# Servos_controller.net
KiCad netlist of a schematic drawn in Altium Designer
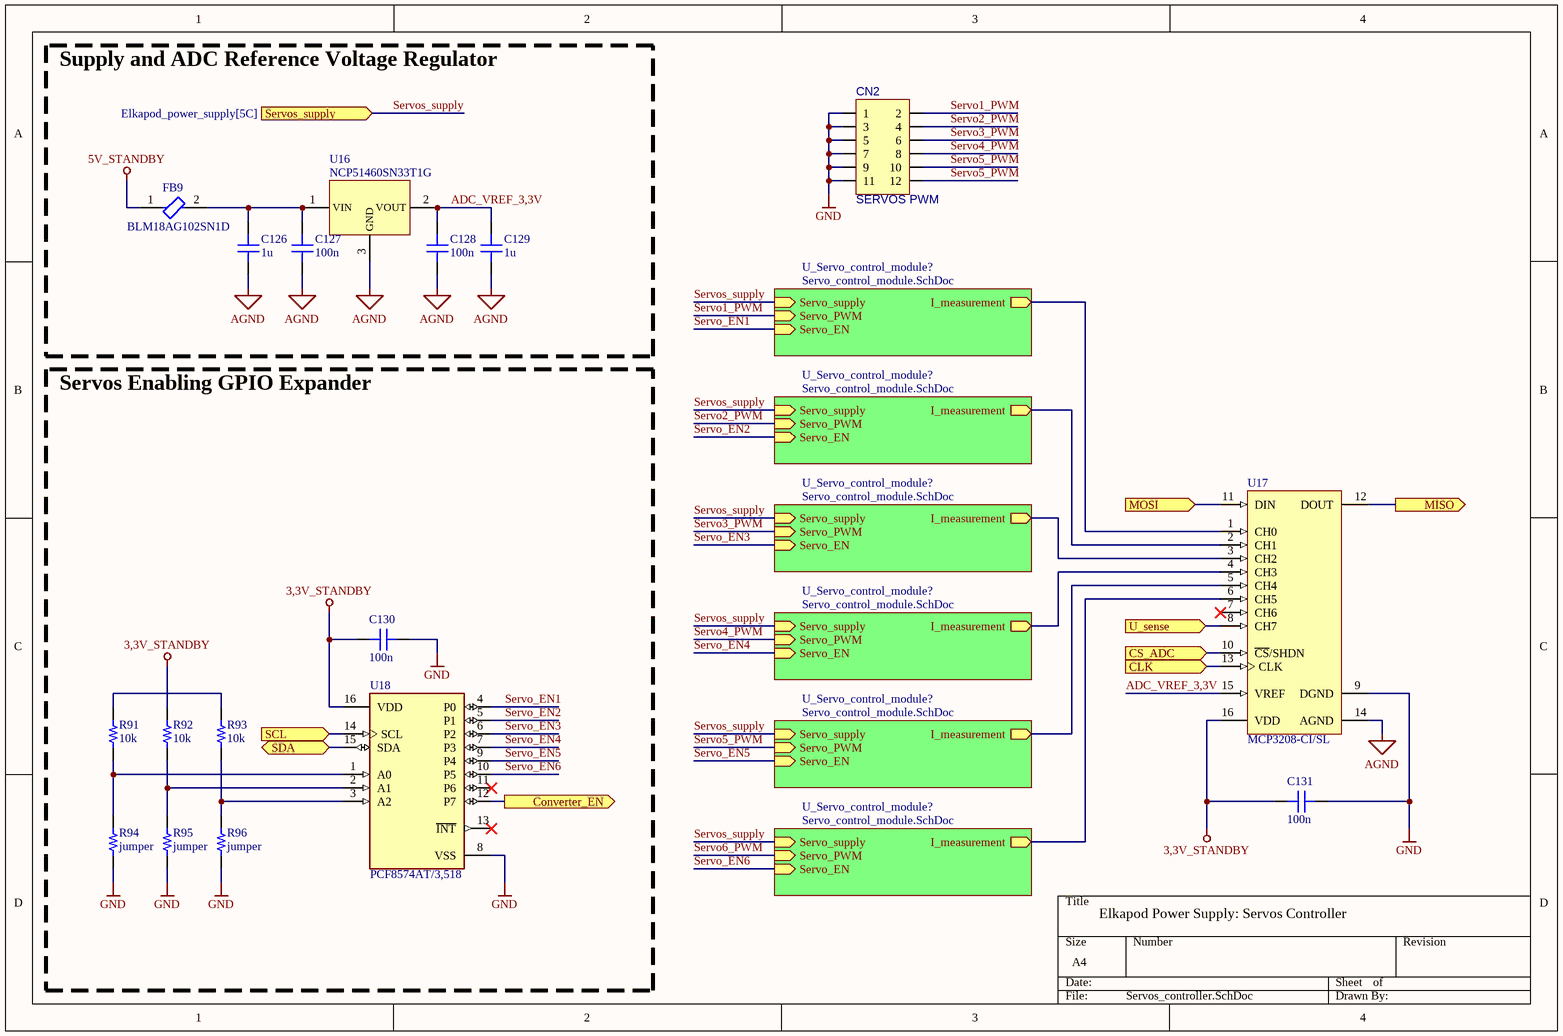
[diagram p0: Servos_controller.SchDoc]

(export (version "E")
  (design (tool "Eeschema 10.0.6"))
  (components
    (comp (ref "C126")
      (value "1u")
      (footprint "CAP 0603_1608")
      (description "CAP CER 1uF 16V X5R 0603")
      (fields (field (name "PART NUMBER") "C0603C272F3GAC7867") (field (name "MANUFACTURER") "KEMET"))
      (libsource (lib "Celestial Altium Library - altium_library") (part "Capacitor"))
    )
    (comp (ref "C127")
      (value "100n")
      (footprint "CAP 0603_1608")
      (description "CAP CER 100nF 25V X5R 0603")
      (fields (field (name "PART NUMBER") "C0603C272F3GAC7867") (field (name "MANUFACTURER") "KEMET"))
      (libsource (lib "Celestial Altium Library - altium_library") (part "Capacitor"))
    )
    (comp (ref "C128")
      (value "100n")
      (footprint "CAP 0603_1608")
      (description "CAP CER 100nF 25V X5R 0603")
      (fields (field (name "PART NUMBER") "C0603C272F3GAC7867") (field (name "MANUFACTURER") "KEMET"))
      (libsource (lib "Celestial Altium Library - altium_library") (part "Capacitor"))
    )
    (comp (ref "C129")
      (value "1u")
      (footprint "CAP 0603_1608")
      (description "CAP CER 1uF 16V X5R 0603")
      (fields (field (name "PART NUMBER") "C0603C272F3GAC7867") (field (name "MANUFACTURER") "KEMET"))
      (libsource (lib "Celestial Altium Library - altium_library") (part "Capacitor"))
    )
    (comp (ref "C130")
      (value "100n")
      (footprint "CAP 0603_1608")
      (description "CAP CER 100nF 25V X5R 0603")
      (fields (field (name "PART NUMBER") "C0603C272F3GAC7867") (field (name "MANUFACTURER") "KEMET"))
      (libsource (lib "Celestial Altium Library - altium_library") (part "Capacitor"))
    )
    (comp (ref "C131")
      (value "100n")
      (footprint "CAP 0603_1608")
      (description "CAP CER 100nF 25V X5R 0603")
      (fields (field (name "PART NUMBER") "C0603C272F3GAC7867") (field (name "MANUFACTURER") "KEMET"))
      (libsource (lib "Celestial Altium Library - altium_library") (part "Capacitor"))
    )
    (comp (ref "CN2") (value "SERVOS PWM") (footprint "IDC12") (libsource (lib "idc") (part "CN_6x2")))
    (comp (ref "FB9")
      (value "BLM18AG102SN1D")
      (footprint "FP-BLM18-0_15-t0_8-MFG")
      (description "Chip Ferrite Bead, 0603, 1000Ω @ 100MHz, 0.5Ω, 25%, 450mA")
      (fields (field (name "TOLERANCE") "25%"))
      (libsource (lib "Altium Content Vault") (part "5f30dd21d616792df468990f7003faa"))
    )
    (comp (ref "R91")
      (value "10k")
      (footprint "RES 0603_1608")
      (description "RES 10K OHM 1% 0,1W 0603")
      (fields
        (field (name "PART NUMBER") "RNCS0603BKE10K0")
        (field (name "MANUFACTURER") "Stackpole Electronics Inc")
      )
      (libsource (lib "Celestial Altium Library - altium_library") (part "Resistor"))
    )
    (comp (ref "R92")
      (value "10k")
      (footprint "RES 0603_1608")
      (description "RES 10K OHM 1% 0,1W 0603")
      (fields
        (field (name "PART NUMBER") "RNCS0603BKE10K0")
        (field (name "MANUFACTURER") "Stackpole Electronics Inc")
      )
      (libsource (lib "Celestial Altium Library - altium_library") (part "Resistor"))
    )
    (comp (ref "R93")
      (value "10k")
      (footprint "RES 0603_1608")
      (description "RES 10K OHM 1% 0,1W 0603")
      (fields
        (field (name "PART NUMBER") "RNCS0603BKE10K0")
        (field (name "MANUFACTURER") "Stackpole Electronics Inc")
      )
      (libsource (lib "Celestial Altium Library - altium_library") (part "Resistor"))
    )
    (comp (ref "R94")
      (value "jumper")
      (footprint "RES 0603_1608")
      (description "RES 0 OHM 1% 0,1W 0603")
      (fields
        (field (name "PART NUMBER") "RNCS0603BKE10K0")
        (field (name "MANUFACTURER") "Stackpole Electronics Inc")
      )
      (libsource (lib "Celestial Altium Library - altium_library") (part "Resistor"))
    )
    (comp (ref "R95")
      (value "jumper")
      (footprint "RES 0603_1608")
      (description "RES 0 OHM 1% 0,1W 0603")
      (fields
        (field (name "PART NUMBER") "RNCS0603BKE10K0")
        (field (name "MANUFACTURER") "Stackpole Electronics Inc")
      )
      (libsource (lib "Celestial Altium Library - altium_library") (part "Resistor"))
    )
    (comp (ref "R96")
      (value "jumper")
      (footprint "RES 0603_1608")
      (description "RES 0 OHM 1% 0,1W 0603")
      (fields
        (field (name "PART NUMBER") "RNCS0603BKE10K0")
        (field (name "MANUFACTURER") "Stackpole Electronics Inc")
      )
      (libsource (lib "Celestial Altium Library - altium_library") (part "Resistor"))
    )
    (comp (ref "U16")
      (value "NCP51460SN33T1G")
      (footprint "SOT23-3")
      (description "Low power precision voltage reference; Iout = 20mA")
      (libsource (lib "My_voltage_regulators") (part "NCP51460SN33T1G"))
    )
    (comp (ref "U17")
      (value "MCP3208-CI/SL")
      (footprint "SOIC-SL16_M")
      (libsource (lib "Altium Content Vault") (part "CON-ADC-MCP3008-16"))
    )
    (comp (ref "U18")
      (value "PCF8574AT/3,518")
      (footprint "FP-SOT162-1-MFG")
      (description "IC I/O EXPANDER I2C 8B 16SOIC")
      (fields
        (field (name "MANUFACTURER") "NXP Semiconductors")
        (field (name "OCTOPART") "https://octopart.com/pcf8574at%2F3%2C518-nxp+semiconductors-11541925")
      )
      (libsource (lib "Altium Content Vault") (part "f7fde53ce59de981fb0b266a4e103eb"))
    )
  )
  (nets
    (net (code "1") (name "/ADC_VREF_3,3V") (class "Default")
      (node (ref "C128") (pin "2") (pinfunction "2_2") (pintype "passive"))
      (node (ref "C129") (pin "2") (pinfunction "2_2") (pintype "passive"))
      (node (ref "U16") (pin "2") (pinfunction "VOUT_2") (pintype "passive"))
      (node (ref "U17") (pin "15") (pinfunction "VREF_15") (pintype "input"))
    )
    (net (code "2") (name "/CLK") (class "Default")
      (node (ref "U17") (pin "13") (pinfunction "CLK_13") (pintype "input"))
    )
    (net (code "3") (name "/CS_ADC") (class "Default")
      (node (ref "U17") (pin "10") (pinfunction "~{CS}/SHDN_10") (pintype "input"))
    )
    (net (code "4") (name "/Converter_EN") (class "Default")
      (node (ref "U18") (pin "12") (pinfunction "P7_12") (pintype "bidirectional"))
    )
    (net (code "5") (name "/I_measurement") (class "Default")
      (node (ref "U17") (pin "3") (pinfunction "CH2_3") (pintype "input"))
    )
    (net (code "6") (name "/I_measurement_1") (class "Default")
      (node (ref "U17") (pin "4") (pinfunction "CH3_4") (pintype "input"))
    )
    (net (code "7") (name "/I_measurement_2") (class "Default")
      (node (ref "U17") (pin "5") (pinfunction "CH4_5") (pintype "input"))
    )
    (net (code "8") (name "/I_measurement_3") (class "Default")
      (node (ref "U17") (pin "6") (pinfunction "CH5_6") (pintype "input"))
    )
    (net (code "9") (name "/I_measurement_4") (class "Default")
      (node (ref "U17") (pin "1") (pinfunction "CH0_1") (pintype "input"))
    )
    (net (code "10") (name "/I_measurement_5") (class "Default")
      (node (ref "U17") (pin "2") (pinfunction "CH1_2") (pintype "input"))
    )
    (net (code "11") (name "/MISO") (class "Default")
      (node (ref "U17") (pin "12") (pinfunction "DOUT_12") (pintype "tri_state"))
    )
    (net (code "12") (name "/MOSI") (class "Default")
      (node (ref "U17") (pin "11") (pinfunction "DIN_11") (pintype "input"))
    )
    (net (code "13") (name "/SCL") (class "Default")
      (node (ref "U18") (pin "14") (pinfunction "SCL_14") (pintype "input"))
    )
    (net (code "14") (name "/SDA") (class "Default")
      (node (ref "U18") (pin "15") (pinfunction "SDA_15") (pintype "bidirectional"))
    )
    (net (code "15") (name "/Servo1_PWM") (class "Default")
      (node (ref "CN2") (pin "2") (pinfunction "2_2") (pintype "passive"))
    )
    (net (code "16") (name "/Servo2_PWM") (class "Default")
      (node (ref "CN2") (pin "4") (pinfunction "4_4") (pintype "passive"))
    )
    (net (code "17") (name "/Servo3_PWM") (class "Default")
      (node (ref "CN2") (pin "6") (pinfunction "6_6") (pintype "passive"))
    )
    (net (code "18") (name "/Servo4_PWM") (class "Default")
      (node (ref "CN2") (pin "8") (pinfunction "8_8") (pintype "passive"))
    )
    (net (code "19") (name "/Servo5_PWM") (class "Default")
      (node (ref "CN2") (pin "10") (pinfunction "10_10") (pintype "passive"))
      (node (ref "CN2") (pin "12") (pinfunction "12_12") (pintype "passive"))
    )
    (net (code "21") (name "/Servo_EN1") (class "Default")
      (node (ref "U18") (pin "4") (pinfunction "P0_4") (pintype "bidirectional"))
    )
    (net (code "22") (name "/Servo_EN2") (class "Default")
      (node (ref "U18") (pin "5") (pinfunction "P1_5") (pintype "bidirectional"))
    )
    (net (code "23") (name "/Servo_EN3") (class "Default")
      (node (ref "U18") (pin "6") (pinfunction "P2_6") (pintype "bidirectional"))
    )
    (net (code "24") (name "/Servo_EN4") (class "Default")
      (node (ref "U18") (pin "7") (pinfunction "P3_7") (pintype "bidirectional"))
    )
    (net (code "25") (name "/Servo_EN5") (class "Default")
      (node (ref "U18") (pin "9") (pinfunction "P4_9") (pintype "bidirectional"))
    )
    (net (code "26") (name "/Servo_EN6") (class "Default")
      (node (ref "U18") (pin "10") (pinfunction "P5_10") (pintype "bidirectional"))
    )
    (net (code "28") (name "/U_sense") (class "Default")
      (node (ref "U17") (pin "8") (pinfunction "CH7_8") (pintype "input"))
    )
    (net (code "29") (name "3,3V_STANDBY") (class "Default")
      (node (ref "C130") (pin "2") (pinfunction "2_2") (pintype "passive"))
      (node (ref "C131") (pin "2") (pinfunction "2_2") (pintype "passive"))
      (node (ref "R92") (pin "1") (pinfunction "1_1") (pintype "passive"))
      (node (ref "U17") (pin "16") (pinfunction "VDD_16") (pintype "power_in"))
      (node (ref "U18") (pin "16") (pinfunction "VDD_16") (pintype "power_in"))
    )
    (net (code "30") (name "5V_STANDBY") (class "Default")
      (node (ref "FB9") (pin "1") (pinfunction "1_1") (pintype "passive"))
    )
    (net (code "31") (name "AGND") (class "Default")
      (node (ref "C126") (pin "1") (pinfunction "1_1") (pintype "passive"))
      (node (ref "C127") (pin "1") (pinfunction "1_1") (pintype "passive"))
      (node (ref "C128") (pin "1") (pinfunction "1_1") (pintype "passive"))
      (node (ref "C129") (pin "1") (pinfunction "1_1") (pintype "passive"))
      (node (ref "U16") (pin "3") (pinfunction "GND_3") (pintype "passive"))
      (node (ref "U17") (pin "14") (pinfunction "AGND_14") (pintype "power_in"))
    )
    (net (code "32") (name "GND") (class "Default")
      (node (ref "C130") (pin "1") (pinfunction "1_1") (pintype "passive"))
      (node (ref "C131") (pin "1") (pinfunction "1_1") (pintype "passive"))
      (node (ref "CN2") (pin "1") (pinfunction "1_1") (pintype "passive"))
      (node (ref "CN2") (pin "11") (pinfunction "11_11") (pintype "passive"))
      (node (ref "CN2") (pin "3") (pinfunction "3_3") (pintype "passive"))
      (node (ref "CN2") (pin "5") (pinfunction "5_5") (pintype "passive"))
      (node (ref "CN2") (pin "7") (pinfunction "7_7") (pintype "passive"))
      (node (ref "CN2") (pin "9") (pinfunction "9_9") (pintype "passive"))
      (node (ref "R94") (pin "2") (pinfunction "2_2") (pintype "passive"))
      (node (ref "R95") (pin "2") (pinfunction "2_2") (pintype "passive"))
      (node (ref "R96") (pin "2") (pinfunction "2_2") (pintype "passive"))
      (node (ref "U17") (pin "9") (pinfunction "DGND_9") (pintype "power_in"))
      (node (ref "U18") (pin "8") (pinfunction "VSS_8") (pintype "power_in"))
    )
    (net (code "33") (name "Net-(R91-Pad1)") (class "Default")
      (node (ref "R91") (pin "1") (pinfunction "1_1") (pintype "passive"))
      (node (ref "R93") (pin "1") (pinfunction "1_1") (pintype "passive"))
    )
    (net (code "34") (name "Net-(U16-VIN)") (class "Default")
      (node (ref "C126") (pin "2") (pinfunction "2_2") (pintype "passive"))
      (node (ref "C127") (pin "2") (pinfunction "2_2") (pintype "passive"))
      (node (ref "FB9") (pin "2") (pinfunction "2_2") (pintype "passive"))
      (node (ref "U16") (pin "1") (pinfunction "VIN_1") (pintype "passive"))
    )
    (net (code "35") (name "Net-(U18-A0)") (class "Default")
      (node (ref "R91") (pin "2") (pinfunction "2_2") (pintype "passive"))
      (node (ref "R94") (pin "1") (pinfunction "1_1") (pintype "passive"))
      (node (ref "U18") (pin "1") (pinfunction "A0_1") (pintype "input"))
    )
    (net (code "36") (name "Net-(U18-A1)") (class "Default")
      (node (ref "R92") (pin "2") (pinfunction "2_2") (pintype "passive"))
      (node (ref "R95") (pin "1") (pinfunction "1_1") (pintype "passive"))
      (node (ref "U18") (pin "2") (pinfunction "A1_2") (pintype "input"))
    )
    (net (code "37") (name "Net-(U18-A2)") (class "Default")
      (node (ref "R93") (pin "2") (pinfunction "2_2") (pintype "passive"))
      (node (ref "R96") (pin "1") (pinfunction "1_1") (pintype "passive"))
      (node (ref "U18") (pin "3") (pinfunction "A2_3") (pintype "input"))
    )
    (net (code "38") (name "unconnected-(U17-CH6-Pad7)") (class "Default")
      (node (ref "U17") (pin "7") (pinfunction "CH6_7") (pintype "input+no_connect"))
    )
    (net (code "39") (name "unconnected-(U18-P6-Pad11)") (class "Default")
      (node (ref "U18") (pin "11") (pinfunction "P6_11") (pintype "bidirectional+no_connect"))
    )
    (net (code "40") (name "unconnected-(U18-~{INT}-Pad13)") (class "Default")
      (node (ref "U18") (pin "13") (pinfunction "~{INT}_13") (pintype "output+no_connect"))
    )
  )
)
